# fiber.net
KiCad netlist of a schematic drawn in Altium Designer
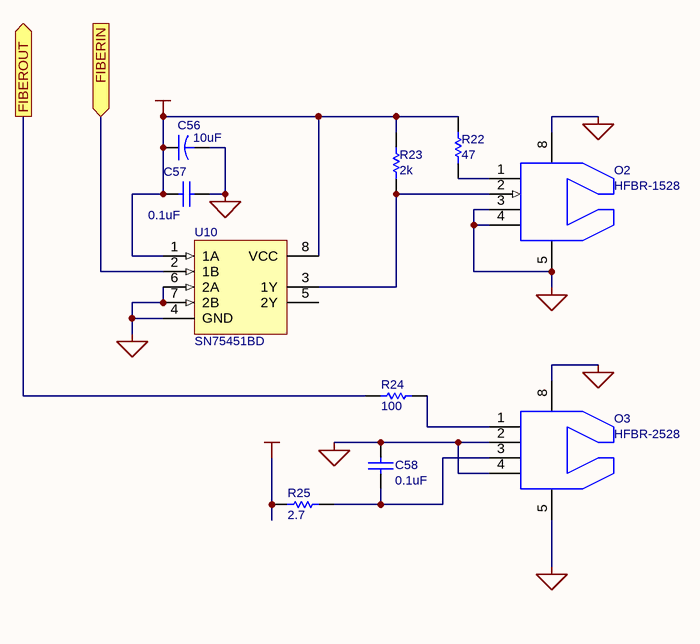
[diagram p0: fiber.SCHDOC]

(export (version "E")
  (design (tool "Eeschema 10.0.6"))
  (components
    (comp (ref "C56")
      (value "10uF")
      (footprint "TC3528-1411")
      (description "Capacitor")
      (fields (field (name "MANUFACTURER") "Generic Components") (field (name "PUBLISHER") "Altium Limited"))
      (libsource (lib "Miscellaneous Devices") (part "Cap2"))
    )
    (comp (ref "C57")
      (value "0.1uF")
      (footprint "CC1005-0402")
      (description "Capacitor")
      (fields
        (field (name "MANUFACTURER") "Generic Components")
        (field (name "Comment") "Cap")
        (field (name "PUBLISHER") "Altium Limited")
      )
      (libsource (lib "Miscellaneous Devices") (part "Cap"))
    )
    (comp (ref "C58")
      (value "0.1uF")
      (footprint "CC1005-0402")
      (description "Capacitor")
      (fields
        (field (name "MANUFACTURER") "Generic Components")
        (field (name "Comment") "Cap")
        (field (name "PUBLISHER") "Altium Limited")
      )
      (libsource (lib "Miscellaneous Devices") (part "Cap"))
    )
    (comp (ref "O2")
      (value "HFBR-1528")
      (footprint "HPVL")
      (description "Low-cost fiber transmitter")
      (libsource (lib "parts") (part "HFBR-1528"))
    )
    (comp (ref "O3")
      (value "HFBR-2528")
      (footprint "HPVL")
      (description "Low-cost fiber receiver")
      (libsource (lib "parts") (part "HFBR-2528"))
    )
    (comp (ref "R22")
      (value "47")
      (footprint "CR1608-0603")
      (description "Resistor")
      (fields
        (field (name "MANUFACTURER") "Generic Components")
        (field (name "Comment") "Res1")
        (field (name "PUBLISHER") "Altium Limited")
      )
      (libsource (lib "Miscellaneous Devices") (part "Res1"))
    )
    (comp (ref "R23")
      (value "2k")
      (footprint "CR1608-0603")
      (description "Resistor")
      (fields
        (field (name "MANUFACTURER") "Generic Components")
        (field (name "Comment") "Res1")
        (field (name "PUBLISHER") "Altium Limited")
      )
      (libsource (lib "Miscellaneous Devices") (part "Res1"))
    )
    (comp (ref "R24")
      (value "100")
      (footprint "CR1608-0603")
      (description "Resistor")
      (fields
        (field (name "MANUFACTURER") "Generic Components")
        (field (name "Comment") "Res1")
        (field (name "PUBLISHER") "Altium Limited")
      )
      (libsource (lib "Miscellaneous Devices") (part "Res1"))
    )
    (comp (ref "R25")
      (value "2.7")
      (footprint "CR1608-0603")
      (description "Resistor")
      (fields
        (field (name "MANUFACTURER") "Generic Components")
        (field (name "Comment") "Res1")
        (field (name "PUBLISHER") "Altium Limited")
      )
      (libsource (lib "Miscellaneous Devices") (part "Res1"))
    )
    (comp (ref "U10")
      (value "SN75451BD")
      (footprint "SO-G8/E2.5")
      (description "Dual Peripheral Driver")
      (fields (field (name "MANUFACTURER") "Texas Instruments") (field (name "PUBLISHER") "Altium Limited"))
      (libsource (lib "TI Interface Peripheral Driver") (part "SN75451BD"))
    )
  )
  (nets
    (net (code "1") (name "+5VCC") (class "Default")
      (node (ref "C56") (pin "1") (pinfunction "1_1") (pintype "passive"))
      (node (ref "C57") (pin "1") (pinfunction "1_1") (pintype "passive"))
      (node (ref "R22") (pin "2") (pinfunction "2_2") (pintype "passive"))
      (node (ref "R23") (pin "2") (pinfunction "2_2") (pintype "passive"))
      (node (ref "R25") (pin "1") (pinfunction "1_1") (pintype "passive"))
      (node (ref "U10") (pin "1") (pinfunction "1A_1") (pintype "input"))
      (node (ref "U10") (pin "8") (pinfunction "VCC_8") (pintype "power_in"))
    )
    (net (code "2") (name "/FIBERIN") (class "Default")
      (node (ref "U10") (pin "2") (pinfunction "1B_2") (pintype "input"))
    )
    (net (code "3") (name "/FIBEROUT") (class "Default")
      (node (ref "R24") (pin "1") (pinfunction "1_1") (pintype "passive"))
    )
    (net (code "4") (name "GND") (class "Default")
      (node (ref "C56") (pin "2") (pinfunction "2_2") (pintype "passive"))
      (node (ref "C57") (pin "2") (pinfunction "2_2") (pintype "passive"))
      (node (ref "C58") (pin "2") (pinfunction "2_2") (pintype "passive"))
      (node (ref "O2") (pin "3") (pintype "power_in"))
      (node (ref "O2") (pin "4") (pintype "power_in"))
      (node (ref "O2") (pin "5") (pintype "power_in"))
      (node (ref "O2") (pin "8") (pintype "power_in"))
      (node (ref "O3") (pin "2") (pintype "power_in"))
      (node (ref "O3") (pin "4") (pintype "power_in"))
      (node (ref "O3") (pin "5") (pintype "power_in"))
      (node (ref "O3") (pin "8") (pintype "power_in"))
      (node (ref "U10") (pin "4") (pinfunction "GND_4") (pintype "power_in"))
      (node (ref "U10") (pin "6") (pinfunction "2A_6") (pintype "input"))
      (node (ref "U10") (pin "7") (pinfunction "2B_7") (pintype "input"))
    )
    (net (code "5") (name "Net-(C58-Pad1)") (class "Default")
      (node (ref "C58") (pin "1") (pinfunction "1_1") (pintype "passive"))
      (node (ref "O3") (pin "3") (pintype "power_in"))
      (node (ref "R25") (pin "2") (pinfunction "2_2") (pintype "passive"))
    )
    (net (code "6") (name "Net-(O2-Pad1)") (class "Default")
      (node (ref "O2") (pin "1") (pintype "power_in"))
      (node (ref "R22") (pin "1") (pinfunction "1_1") (pintype "passive"))
    )
    (net (code "7") (name "Net-(O3-Pad1)") (class "Default")
      (node (ref "O3") (pin "1") (pintype "power_in"))
      (node (ref "R24") (pin "2") (pinfunction "2_2") (pintype "passive"))
    )
    (net (code "8") (name "Net-(U10-1Y)") (class "Default")
      (node (ref "O2") (pin "2") (pintype "input"))
      (node (ref "R23") (pin "1") (pinfunction "1_1") (pintype "passive"))
      (node (ref "U10") (pin "3") (pinfunction "1Y_3") (pintype "open_collector"))
    )
    (net (code "9") (name "unconnected-(U10-2Y-Pad5)") (class "Default")
      (node (ref "U10") (pin "5") (pinfunction "2Y_5") (pintype "open_collector"))
    )
  )
)
